# PDC_Gate_Driver.net
KiCad netlist of a schematic drawn in Altium Designer
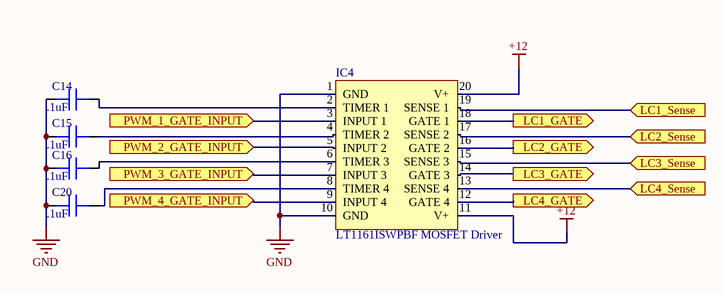
[diagram p0: PDC_Gate_Driver.SchDoc]

(export (version "E")
  (design (tool "Eeschema 10.0.6"))
  (components
    (comp (ref "C14")
      (value "capacitor")
      (footprint "0603")
      (description "Generic 0603 capacitor")
      (fields (field (name "CAPACITANCE") ".1uF") (field (name "VOLTAGE") "50"))
      (libsource (lib "altlib") (part "capacitor"))
    )
    (comp (ref "C15")
      (value "capacitor")
      (footprint "0603")
      (description "Generic 0603 capacitor")
      (fields (field (name "CAPACITANCE") ".1uF") (field (name "VOLTAGE") "50"))
      (libsource (lib "altlib") (part "capacitor"))
    )
    (comp (ref "C16")
      (value "capacitor")
      (footprint "0603")
      (description "Generic 0603 capacitor")
      (fields (field (name "CAPACITANCE") ".1uF") (field (name "VOLTAGE") "50"))
      (libsource (lib "altlib") (part "capacitor"))
    )
    (comp (ref "C20")
      (value "capacitor")
      (footprint "0603")
      (description "Generic 0603 capacitor")
      (fields (field (name "CAPACITANCE") ".1uF") (field (name "VOLTAGE") "50"))
      (libsource (lib "altlib") (part "capacitor"))
    )
    (comp (ref "IC4")
      (value "LT1161ISWPBF MOSFET Driver")
      (footprint "SO-20")
      (fields (field (name "CREATED_BY") "Eunice Bernardo"))
      (libsource (lib "Altium-Lib") (part "LT1161ISWPBF MOSFET Driver"))
    )
  )
  (nets
    (net (code "1") (name "+12") (class "Default")
      (node (ref "IC4") (pin "11") (pinfunction "V+_11") (pintype "input"))
      (node (ref "IC4") (pin "20") (pinfunction "V+_20") (pintype "input"))
    )
    (net (code "2") (name "/LC1_GATE") (class "Default")
      (node (ref "IC4") (pin "18") (pinfunction "GATE_1_18") (pintype "input"))
    )
    (net (code "3") (name "/LC1_Sense") (class "Default")
      (node (ref "IC4") (pin "19") (pinfunction "SENSE_1_19") (pintype "input"))
    )
    (net (code "4") (name "/LC2_GATE") (class "Default")
      (node (ref "IC4") (pin "16") (pinfunction "GATE_2_16") (pintype "input"))
    )
    (net (code "5") (name "/LC2_Sense") (class "Default")
      (node (ref "IC4") (pin "17") (pinfunction "SENSE_2_17") (pintype "input"))
    )
    (net (code "6") (name "/LC3_GATE") (class "Default")
      (node (ref "IC4") (pin "14") (pinfunction "GATE_3_14") (pintype "input"))
    )
    (net (code "7") (name "/LC3_Sense") (class "Default")
      (node (ref "IC4") (pin "15") (pinfunction "SENSE_3_15") (pintype "input"))
    )
    (net (code "8") (name "/LC4_GATE") (class "Default")
      (node (ref "IC4") (pin "12") (pinfunction "GATE_4_12") (pintype "input"))
    )
    (net (code "9") (name "/LC4_Sense") (class "Default")
      (node (ref "IC4") (pin "13") (pinfunction "SENSE_4_13") (pintype "input"))
    )
    (net (code "10") (name "/PWM_1_GATE_INPUT") (class "Default")
      (node (ref "IC4") (pin "3") (pinfunction "INPUT_1_3") (pintype "input"))
    )
    (net (code "11") (name "/PWM_2_GATE_INPUT") (class "Default")
      (node (ref "IC4") (pin "5") (pinfunction "INPUT_2_5") (pintype "input"))
    )
    (net (code "12") (name "/PWM_3_GATE_INPUT") (class "Default")
      (node (ref "IC4") (pin "7") (pinfunction "INPUT_3_7") (pintype "input"))
    )
    (net (code "13") (name "/PWM_4_GATE_INPUT") (class "Default")
      (node (ref "IC4") (pin "9") (pinfunction "INPUT_4_9") (pintype "input"))
    )
    (net (code "14") (name "GND") (class "Default")
      (node (ref "C14") (pin "1") (pinfunction "1_1") (pintype "passive"))
      (node (ref "C15") (pin "1") (pinfunction "1_1") (pintype "passive"))
      (node (ref "C16") (pin "1") (pinfunction "1_1") (pintype "passive"))
      (node (ref "C20") (pin "1") (pinfunction "1_1") (pintype "passive"))
      (node (ref "IC4") (pin "1") (pinfunction "GND_1") (pintype "input"))
      (node (ref "IC4") (pin "10") (pinfunction "GND_10") (pintype "input"))
    )
    (net (code "15") (name "Net-(IC4-TIMER_1)") (class "Default")
      (node (ref "C14") (pin "2") (pinfunction "2_2") (pintype "passive"))
      (node (ref "IC4") (pin "2") (pinfunction "TIMER_1_2") (pintype "input"))
    )
    (net (code "16") (name "Net-(IC4-TIMER_2)") (class "Default")
      (node (ref "C15") (pin "2") (pinfunction "2_2") (pintype "passive"))
      (node (ref "IC4") (pin "4") (pinfunction "TIMER_2_4") (pintype "input"))
    )
    (net (code "17") (name "Net-(IC4-TIMER_3)") (class "Default")
      (node (ref "C16") (pin "2") (pinfunction "2_2") (pintype "passive"))
      (node (ref "IC4") (pin "6") (pinfunction "TIMER_3_6") (pintype "input"))
    )
    (net (code "18") (name "Net-(IC4-TIMER_4)") (class "Default")
      (node (ref "C20") (pin "2") (pinfunction "2_2") (pintype "passive"))
      (node (ref "IC4") (pin "8") (pinfunction "TIMER_4_8") (pintype "input"))
    )
  )
)
